# Multiband_XOver_filter.net
KiCad netlist of a schematic drawn in Altium Designer
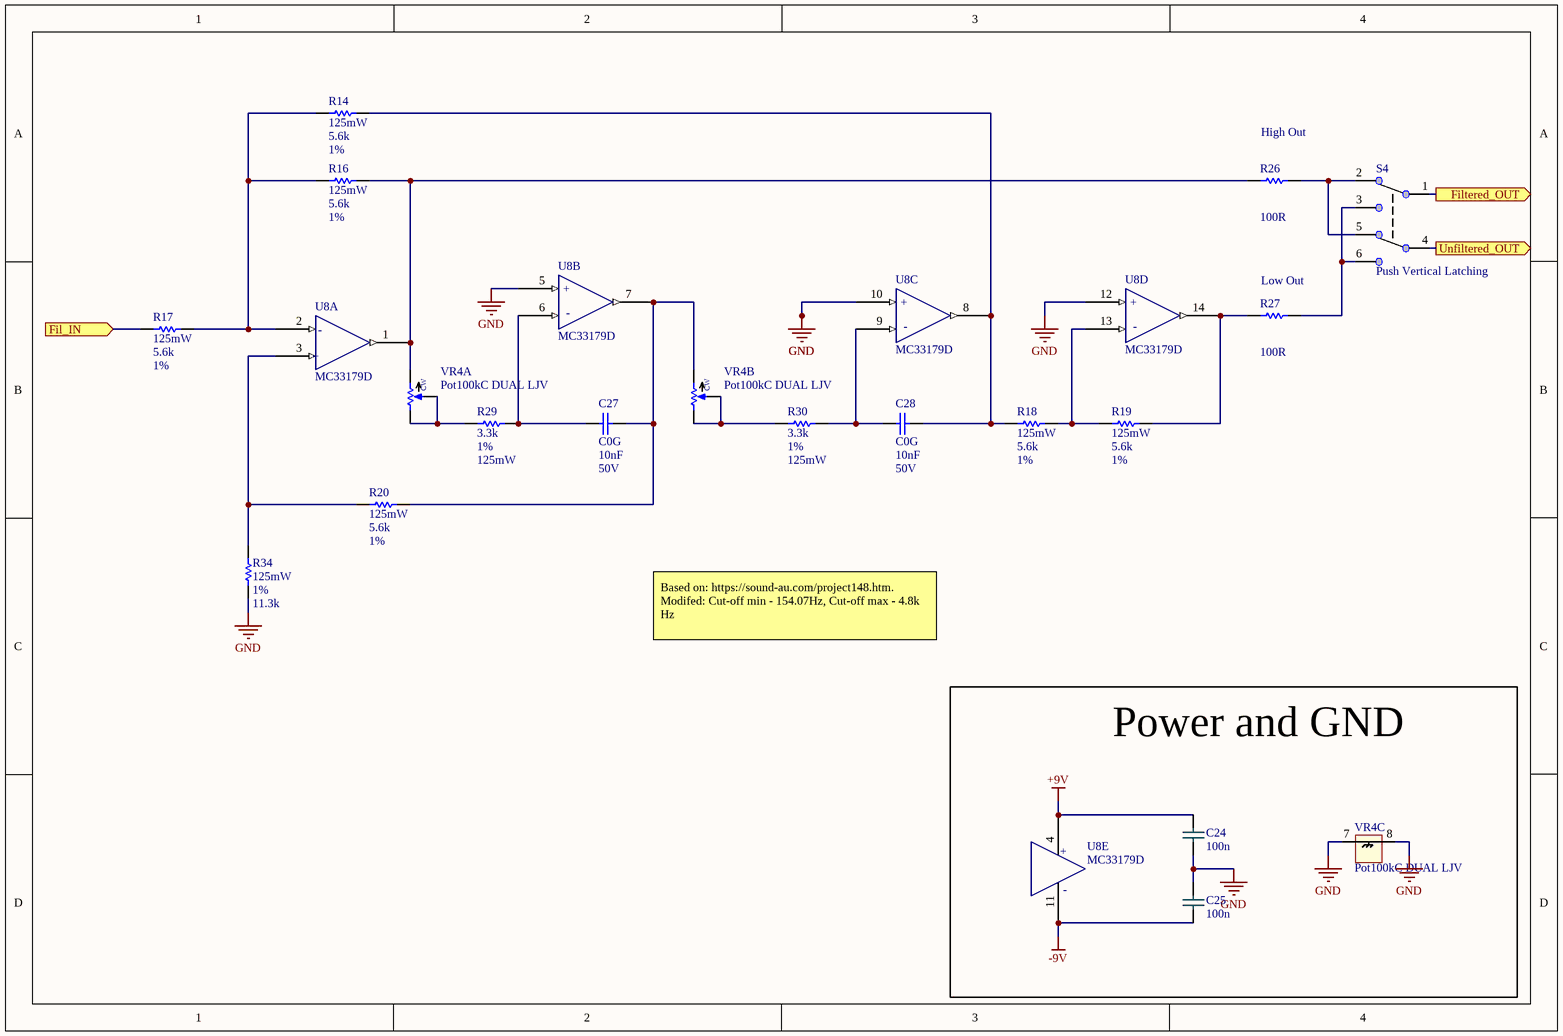
[diagram p0: Multiband XOver filter.SchDoc]

(export (version "E")
  (design (tool "Eeschema 10.0.6"))
  (components
    (comp (ref "C24")
      (value "100n")
      (footprint "0805-CAP")
      (description "0.1uF 25volts C0G 5%")
      (fields
        (field (name "MOUSER PART") "81-GRM31C5C1E104JA01")
        (field (name "Comment") "Cap 0805 100nF 4")
        (field (name "PUBLISHER") "Altium Limited")
      )
      (libsource (lib "Darkglass Electronics") (part "Capacitor NP"))
    )
    (comp (ref "C25")
      (value "100n")
      (footprint "0805-CAP")
      (description "0.1uF 25volts C0G 5%")
      (fields
        (field (name "MOUSER PART") "81-GRM31C5C1E104JA01")
        (field (name "Comment") "Cap 0805 100nF 4")
        (field (name "PUBLISHER") "Altium Limited")
      )
      (libsource (lib "Darkglass Electronics") (part "Capacitor NP"))
    )
    (comp (ref "C27")
      (value "Cap 10nF 0805 C0G")
      (footprint "0805-CAP")
      (description "Cap 10nF 0805 C0G 50V +-5%")
      (fields
        (field (name "DIELECTRIC") "C0G")
        (field (name "CAPACITANCE") "10nF")
        (field (name "RATED VOLTAGE") "50V")
      )
      (libsource (lib "Darkglass Electronics") (part "Capacitor Non-polarized"))
    )
    (comp (ref "C28")
      (value "Cap 10nF 0805 C0G")
      (footprint "0805-CAP")
      (description "Cap 10nF 0805 C0G 50V +-5%")
      (fields
        (field (name "DIELECTRIC") "C0G")
        (field (name "CAPACITANCE") "10nF")
        (field (name "RATED VOLTAGE") "50V")
      )
      (libsource (lib "Darkglass Electronics") (part "Capacitor Non-polarized"))
    )
    (comp (ref "R14")
      (value "Res 5.6k 1% 0805")
      (footprint "0805-RES")
      (description "Resistor 5.6k +-1% 0805 Thin film 0.125W +-50ppm/°C")
      (fields
        (field (name "POWER") "125mW")
        (field (name "RESISTANCE") "5.6k")
        (field (name "TOLERANCE (+-)") "1%")
      )
      (libsource (lib "Darkglass Electronics") (part "Resistor"))
    )
    (comp (ref "R16")
      (value "Res 5.6k 1% 0805")
      (footprint "0805-RES")
      (description "Resistor 5.6k +-1% 0805 Thin film 0.125W +-50ppm/°C")
      (fields
        (field (name "POWER") "125mW")
        (field (name "RESISTANCE") "5.6k")
        (field (name "TOLERANCE (+-)") "1%")
      )
      (libsource (lib "Darkglass Electronics") (part "Resistor"))
    )
    (comp (ref "R17")
      (value "Res 5.6k 1% 0805")
      (footprint "0805-RES")
      (description "Resistor 5.6k +-1% 0805 Thin film 0.125W +-50ppm/°C")
      (fields
        (field (name "POWER") "125mW")
        (field (name "RESISTANCE") "5.6k")
        (field (name "TOLERANCE (+-)") "1%")
      )
      (libsource (lib "Darkglass Electronics") (part "Resistor"))
    )
    (comp (ref "R18")
      (value "Res 5.6k 1% 0805")
      (footprint "0805-RES")
      (description "Resistor 5.6k +-1% 0805 Thin film 0.125W +-50ppm/°C")
      (fields
        (field (name "POWER") "125mW")
        (field (name "RESISTANCE") "5.6k")
        (field (name "TOLERANCE (+-)") "1%")
      )
      (libsource (lib "Darkglass Electronics") (part "Resistor"))
    )
    (comp (ref "R19")
      (value "Res 5.6k 1% 0805")
      (footprint "0805-RES")
      (description "Resistor 5.6k +-1% 0805 Thin film 0.125W +-50ppm/°C")
      (fields
        (field (name "POWER") "125mW")
        (field (name "RESISTANCE") "5.6k")
        (field (name "TOLERANCE (+-)") "1%")
      )
      (libsource (lib "Darkglass Electronics") (part "Resistor"))
    )
    (comp (ref "R20")
      (value "Res 5.6k 1% 0805")
      (footprint "0805-RES")
      (description "Resistor 5.6k +-1% 0805 Thin film 0.125W +-50ppm/°C")
      (fields
        (field (name "POWER") "125mW")
        (field (name "RESISTANCE") "5.6k")
        (field (name "TOLERANCE (+-)") "1%")
      )
      (libsource (lib "Darkglass Electronics") (part "Resistor"))
    )
    (comp (ref "R26")
      (value "Res 0805 100R 1%")
      (footprint "0805-RES")
      (description "100ohm, 125mW, 1%, thin film")
      (fields
        (field (name "RESISTANCE") "100R")
        (field (name "TOLERANCE") "1%")
        (field (name "PUBLISHER") "Altium Limited")
      )
      (libsource (lib "Darkglass Electronics") (part "RES"))
    )
    (comp (ref "R27")
      (value "Res 0805 100R 1%")
      (footprint "0805-RES")
      (description "100ohm, 125mW, 1%, thin film")
      (fields
        (field (name "RESISTANCE") "100R")
        (field (name "TOLERANCE") "1%")
        (field (name "PUBLISHER") "Altium Limited")
      )
      (libsource (lib "Darkglass Electronics") (part "RES"))
    )
    (comp (ref "R29")
      (value "Res 3.3k 1% 0805")
      (footprint "0805-RES")
      (description "Resistor 3.3k +-1% 0805 Thin film 0.125W +-50ppm/°C")
      (fields
        (field (name "RESISTANCE") "3.3k")
        (field (name "TOLERANCE (+-)") "1%")
        (field (name "POWER") "125mW")
      )
      (libsource (lib "Darkglass Electronics") (part "Resistor"))
    )
    (comp (ref "R30")
      (value "Res 3.3k 1% 0805")
      (footprint "0805-RES")
      (description "Resistor 3.3k +-1% 0805 Thin film 0.125W +-50ppm/°C")
      (fields
        (field (name "RESISTANCE") "3.3k")
        (field (name "TOLERANCE (+-)") "1%")
        (field (name "POWER") "125mW")
      )
      (libsource (lib "Darkglass Electronics") (part "Resistor"))
    )
    (comp (ref "R34")
      (value "Res 11.3k 1% 0805")
      (footprint "0805-RES")
      (description "Resistor 11.3k +-1% 0805 Thin film 0.125W +-50ppm/°C")
      (fields
        (field (name "POWER") "125mW")
        (field (name "TOLERANCE (+-)") "1%")
        (field (name "RESISTANCE") "11.3k")
      )
      (libsource (lib "Darkglass Electronics") (part "Resistor"))
    )
    (comp (ref "S4")
      (value "Push Vertical Latching")
      (footprint "PUSH VERTICAL DPDT")
      (description "DPDT Pushbutton Latching")
      (fields
        (field (name "MANUFACTURER PART NUMBER") "TL2201EEXA")
        (field (name "DARKGLASS PART") "D00-0005")
      )
      (libsource (lib "Darkglass Electronics") (part "Push Vertical"))
    )
    (comp (ref "U8")
      (value "MC33179D")
      (footprint "SOIC14-127P600X175-14N")
      (description "Operational Amplifiers - Op Amps 2-18V Quad Low Power Industrial Temp SOIC14")
      (fields
        (field (name "MANUFACTURER PART NUMBER") "MC33179DR2G")
        (field (name "MANUFACTURER") "ON Semiconductor")
      )
      (libsource (lib "Darkglass Electronics") (part "Symbol"))
    )
    (comp (ref "VR4")
      (value "Pot100kC DUAL LJV")
      (footprint "LJV 9MM DUAL")
      (description "Dual gang rev log pot")
      (libsource (lib "Darkglass Electronics") (part "Pot100kC DUAL LJV"))
    )
  )
  (nets
    (net (code "1") (name "+9V") (class "Default")
      (node (ref "C24") (pin "2") (pinfunction "2_2") (pintype "passive"))
      (node (ref "U8") (pin "4") (pinfunction "4_4") (pintype "power_in"))
    )
    (net (code "2") (name "-9V") (class "Default")
      (node (ref "C25") (pin "1") (pinfunction "1_1") (pintype "passive"))
      (node (ref "U8") (pin "11") (pinfunction "11_11") (pintype "power_in"))
    )
    (net (code "3") (name "/Fil_IN") (class "Default")
      (node (ref "R17") (pin "1") (pinfunction "1_1") (pintype "passive"))
    )
    (net (code "4") (name "/Filtered_OUT") (class "Default")
      (node (ref "S4") (pin "1") (pinfunction "1_1") (pintype "passive"))
    )
    (net (code "5") (name "/Unfiltered_OUT") (class "Default")
      (node (ref "S4") (pin "4") (pinfunction "4_4") (pintype "passive"))
    )
    (net (code "6") (name "GND") (class "Default")
      (node (ref "C24") (pin "1") (pinfunction "1_1") (pintype "passive"))
      (node (ref "C25") (pin "2") (pinfunction "2_2") (pintype "passive"))
      (node (ref "R34") (pin "2") (pinfunction "2_2") (pintype "passive"))
      (node (ref "U8") (pin "10") (pinfunction "10_10") (pintype "input"))
      (node (ref "U8") (pin "12") (pinfunction "12_12") (pintype "input"))
      (node (ref "U8") (pin "5") (pinfunction "5_5") (pintype "input"))
      (node (ref "VR4") (pin "7") (pinfunction "7_7") (pintype "passive"))
      (node (ref "VR4") (pin "8") (pinfunction "8_8") (pintype "passive"))
    )
    (net (code "7") (name "Net-(C27-Pad1)") (class "Default")
      (node (ref "C27") (pin "1") (pinfunction "1_1") (pintype "passive"))
      (node (ref "R29") (pin "2") (pinfunction "2_2") (pintype "passive"))
      (node (ref "U8") (pin "6") (pinfunction "6_6") (pintype "input"))
    )
    (net (code "8") (name "Net-(C28-Pad1)") (class "Default")
      (node (ref "C28") (pin "1") (pinfunction "1_1") (pintype "passive"))
      (node (ref "R30") (pin "2") (pinfunction "2_2") (pintype "passive"))
      (node (ref "U8") (pin "9") (pinfunction "9_9") (pintype "input"))
    )
    (net (code "9") (name "Net-(C28-Pad2)") (class "Default")
      (node (ref "C28") (pin "2") (pinfunction "2_2") (pintype "passive"))
      (node (ref "R14") (pin "2") (pinfunction "2_2") (pintype "passive"))
      (node (ref "R18") (pin "1") (pinfunction "1_1") (pintype "passive"))
      (node (ref "U8") (pin "8") (pinfunction "8_8") (pintype "output"))
    )
    (net (code "10") (name "Net-(R14-Pad1)") (class "Default")
      (node (ref "R14") (pin "1") (pinfunction "1_1") (pintype "passive"))
      (node (ref "R16") (pin "1") (pinfunction "1_1") (pintype "passive"))
      (node (ref "R17") (pin "2") (pinfunction "2_2") (pintype "passive"))
      (node (ref "U8") (pin "2") (pinfunction "2_2") (pintype "input"))
    )
    (net (code "11") (name "Net-(R18-Pad2)") (class "Default")
      (node (ref "R18") (pin "2") (pinfunction "2_2") (pintype "passive"))
      (node (ref "R19") (pin "1") (pinfunction "1_1") (pintype "passive"))
      (node (ref "U8") (pin "13") (pinfunction "13_13") (pintype "input"))
    )
    (net (code "12") (name "Net-(R19-Pad2)") (class "Default")
      (node (ref "R19") (pin "2") (pinfunction "2_2") (pintype "passive"))
      (node (ref "R27") (pin "2") (pinfunction "2_2") (pintype "passive"))
      (node (ref "U8") (pin "14") (pinfunction "14_14") (pintype "output"))
    )
    (net (code "13") (name "Net-(R20-Pad1)") (class "Default")
      (node (ref "R20") (pin "1") (pinfunction "1_1") (pintype "passive"))
      (node (ref "R34") (pin "1") (pinfunction "1_1") (pintype "passive"))
      (node (ref "U8") (pin "3") (pinfunction "3_3") (pintype "input"))
    )
    (net (code "14") (name "Net-(R26-Pad1)") (class "Default")
      (node (ref "R26") (pin "1") (pinfunction "1_1") (pintype "passive"))
      (node (ref "S4") (pin "2") (pinfunction "2_2") (pintype "passive"))
      (node (ref "S4") (pin "5") (pinfunction "5_5") (pintype "passive"))
    )
    (net (code "15") (name "Net-(R27-Pad1)") (class "Default")
      (node (ref "R27") (pin "1") (pinfunction "1_1") (pintype "passive"))
      (node (ref "S4") (pin "3") (pinfunction "3_3") (pintype "passive"))
      (node (ref "S4") (pin "6") (pinfunction "6_6") (pintype "passive"))
    )
    (net (code "16") (name "Net-(VR4A-CCWPIN)") (class "Default")
      (node (ref "R29") (pin "1") (pinfunction "1_1") (pintype "passive"))
      (node (ref "VR4") (pin "1") (pinfunction "CCWPIN_1") (pintype "passive"))
      (node (ref "VR4") (pin "2") (pinfunction "WIPER_2") (pintype "passive"))
    )
    (net (code "17") (name "Net-(VR4A-CWPIN)") (class "Default")
      (node (ref "R16") (pin "2") (pinfunction "2_2") (pintype "passive"))
      (node (ref "R26") (pin "2") (pinfunction "2_2") (pintype "passive"))
      (node (ref "U8") (pin "1") (pinfunction "1_1") (pintype "output"))
      (node (ref "VR4") (pin "3") (pinfunction "CWPIN_3") (pintype "passive"))
    )
    (net (code "18") (name "Net-(VR4B-CCWPIN)") (class "Default")
      (node (ref "R30") (pin "1") (pinfunction "1_1") (pintype "passive"))
      (node (ref "VR4") (pin "4") (pinfunction "CCWPIN_4") (pintype "passive"))
      (node (ref "VR4") (pin "5") (pinfunction "WIPER_5") (pintype "passive"))
    )
    (net (code "19") (name "Net-(VR4B-CWPIN)") (class "Default")
      (node (ref "C27") (pin "2") (pinfunction "2_2") (pintype "passive"))
      (node (ref "R20") (pin "2") (pinfunction "2_2") (pintype "passive"))
      (node (ref "U8") (pin "7") (pinfunction "7_7") (pintype "output"))
      (node (ref "VR4") (pin "6") (pinfunction "CWPIN_6") (pintype "passive"))
    )
  )
)
